# 2015_Rx24Duplicator.net
KiCad netlist of a schematic drawn in Altium Designer
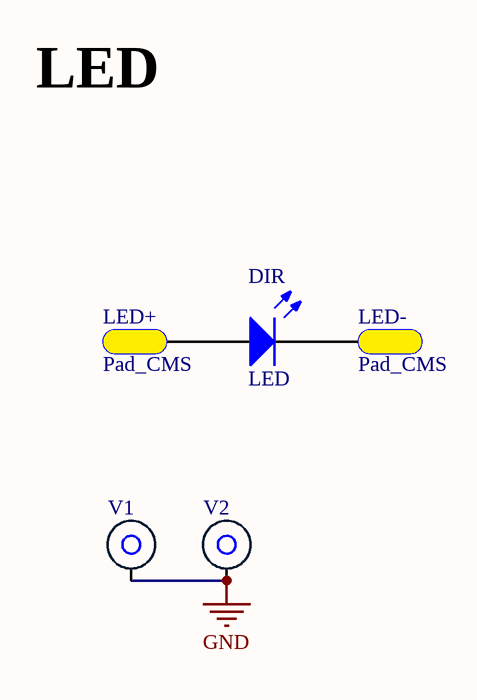
[diagram p0: 2015_Rx24Duplicator.SchDoc]

(export (version "E")
  (design (tool "Eeschema 10.0.6"))
  (components
    (comp (ref "DIR")
      (value "LED")
      (footprint "Led_5mm")
      (description "Typical RED, GREEN, YELLOW, AMBER GaAs LED")
      (fields (field (name "PUBLISHER") "Altium Limited"))
      (libsource (lib "Robot2010") (part "LED"))
    )
    (comp (ref "LED+")
      (value "Pad_CMS")
      (footprint "PAD_CMS_5.08x2.54")
      (description "Pad pour souder un fil")
      (fields (field (name "PUBLISHER") "Damien Guitton"))
      (libsource (lib "DG_Connecteur") (part "Pad_CMS"))
    )
    (comp (ref "LED-")
      (value "Pad_CMS")
      (footprint "PAD_CMS_5.08x2.54")
      (description "Pad pour souder un fil")
      (fields (field (name "PUBLISHER") "Damien Guitton"))
      (libsource (lib "DG_Connecteur") (part "Pad_CMS"))
    )
    (comp (ref "V1")
      (value "Entretoise WURTH CMS")
      (footprint "ENTRETOISE_CMS")
      (description "Entretoise Wurth")
      (fields (field (name "PUBLISHER") "Damien Guitton"))
      (libsource (lib "_ROBOT") (part "Entretoise WURTH CMS"))
    )
    (comp (ref "V2")
      (value "Entretoise WURTH CMS")
      (footprint "ENTRETOISE_CMS")
      (description "Entretoise Wurth")
      (fields (field (name "PUBLISHER") "Damien Guitton"))
      (libsource (lib "_ROBOT") (part "Entretoise WURTH CMS"))
    )
  )
  (nets
    (net (code "1") (name "GND") (class "Default")
      (node (ref "V1") (pin "1") (pinfunction "1_1") (pintype "passive"))
      (node (ref "V2") (pin "1") (pinfunction "1_1") (pintype "passive"))
    )
    (net (code "2") (name "Net-(DIR-Pad1)") (class "Default")
      (node (ref "DIR") (pin "1") (pinfunction "1_1") (pintype "passive"))
      (node (ref "LED+") (pin "1") (pinfunction "1_1") (pintype "passive"))
    )
    (net (code "3") (name "Net-(DIR-Pad2)") (class "Default")
      (node (ref "DIR") (pin "2") (pinfunction "2_2") (pintype "passive"))
      (node (ref "LED-") (pin "1") (pinfunction "1_1") (pintype "passive"))
    )
  )
)
